# Adapter-Stamps-005.net
KiCad netlist of a schematic drawn in EAGLE
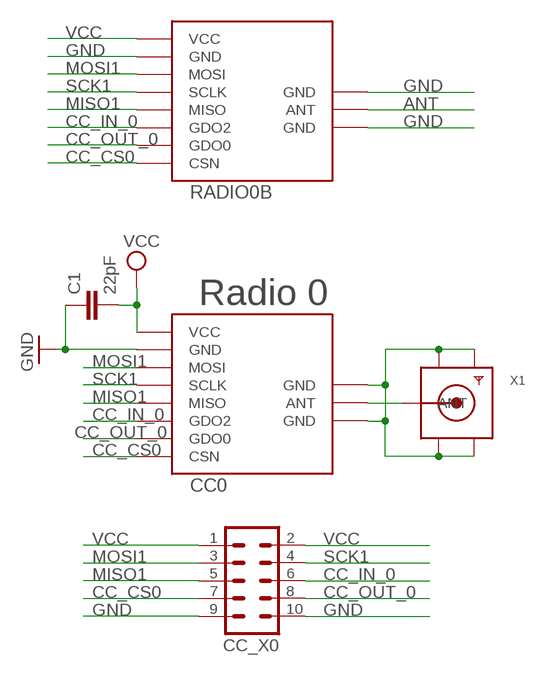
[diagram p0: schematic, sheet 1]

(export (version "E")
  (design (tool "Eeschema 10.0.6"))
  (components
    (comp (ref "C1")
      (value "22pF")
      (footprint "eagle-import:C0805")
      (libsource (lib "eagle-import") (part "C-EUC0805"))
    )
    (comp (ref "CC0")
      (value "CC1101_MODULE1SMD")
      (footprint "eagle-import:CC1101_MODULE1_SMD")
      (libsource (lib "eagle-import") (part "wireless_CC1101_MODULE1SMD"))
    )
    (comp (ref "CC_X0")
      (value "MA05-2")
      (footprint "eagle-import:MA05-2")
      (libsource (lib "eagle-import") (part "MA05-2"))
    )
    (comp (ref "RADIO0B")
      (value "CC1101_MODULE1SMALL")
      (footprint "eagle-import:CC1101_MODULE1_SMD")
      (libsource (lib "eagle-import") (part "CC1101_MODULE1SMALL"))
    )
    (comp (ref "X1")
      (value "SMACONNECTOR_EDGE_UFL")
      (footprint "eagle-import:SMA_EDGELAUNCH_UFL")
      (libsource (lib "eagle-import") (part "SMACONNECTOR_EDGE_UFL"))
    )
  )
  (nets
    (net (code "1") (name "/ANT") (class "Default")
      (node (ref "RADIO0B") (pin "ANT") (pinfunction "ANT_ANT") (pintype "output"))
    )
    (net (code "2") (name "/CC_CS0") (class "Default")
      (node (ref "CC0") (pin "CSN") (pinfunction "CSN_CSN") (pintype "bidirectional"))
      (node (ref "CC_X0") (pin "7") (pinfunction "7_7") (pintype "passive"))
      (node (ref "RADIO0B") (pin "CSN") (pinfunction "CSN_CSN") (pintype "bidirectional"))
    )
    (net (code "3") (name "/CC_IN_0") (class "Default")
      (node (ref "CC0") (pin "GDO2") (pinfunction "GDO2_GDO2") (pintype "bidirectional"))
      (node (ref "CC_X0") (pin "6") (pinfunction "6_6") (pintype "passive"))
      (node (ref "RADIO0B") (pin "GDO2") (pinfunction "GDO2_GDO2") (pintype "bidirectional"))
    )
    (net (code "4") (name "/CC_OUT_0") (class "Default")
      (node (ref "CC0") (pin "GDO0") (pinfunction "GDO0_GDO0") (pintype "bidirectional"))
      (node (ref "CC_X0") (pin "8") (pinfunction "8_8") (pintype "passive"))
      (node (ref "RADIO0B") (pin "GDO0") (pinfunction "GDO0_GDO0") (pintype "bidirectional"))
    )
    (net (code "5") (name "/MISO1") (class "Default")
      (node (ref "CC0") (pin "MISO") (pinfunction "MISO_MISO") (pintype "bidirectional"))
      (node (ref "CC_X0") (pin "5") (pinfunction "5_5") (pintype "passive"))
      (node (ref "RADIO0B") (pin "MISO") (pinfunction "MISO_MISO") (pintype "bidirectional"))
    )
    (net (code "6") (name "/MOSI1") (class "Default")
      (node (ref "CC0") (pin "MOSI") (pinfunction "MOSI_MOSI") (pintype "bidirectional"))
      (node (ref "CC_X0") (pin "3") (pinfunction "3_3") (pintype "passive"))
      (node (ref "RADIO0B") (pin "MOSI") (pinfunction "MOSI_MOSI") (pintype "bidirectional"))
    )
    (net (code "7") (name "/SCK1") (class "Default")
      (node (ref "CC0") (pin "SCLK") (pinfunction "SCLK_SCLK") (pintype "bidirectional"))
      (node (ref "CC_X0") (pin "4") (pinfunction "4_4") (pintype "passive"))
      (node (ref "RADIO0B") (pin "SCLK") (pinfunction "SCLK_SCLK") (pintype "bidirectional"))
    )
    (net (code "8") (name "GND") (class "Default")
      (node (ref "C1") (pin "1") (pinfunction "1_1") (pintype "passive"))
      (node (ref "CC0") (pin "GND@0") (pinfunction "GND_GND@0") (pintype "power_in"))
      (node (ref "CC_X0") (pin "10") (pinfunction "10_10") (pintype "passive"))
      (node (ref "CC_X0") (pin "9") (pinfunction "9_9") (pintype "passive"))
      (node (ref "RADIO0B") (pin "GND@0") (pinfunction "GND_GND@0") (pintype "power_in"))
      (node (ref "RADIO0B") (pin "GND@1") (pinfunction "GND_GND@1") (pintype "power_in"))
      (node (ref "RADIO0B") (pin "GND@2") (pinfunction "GND_GND@2") (pintype "power_in"))
    )
    (net (code "9") (name "Net-(X1-ANT)") (class "Default")
      (node (ref "CC0") (pin "ANT") (pinfunction "ANT_ANT") (pintype "output"))
      (node (ref "X1") (pin "P") (pinfunction "ANT_P") (pintype "bidirectional"))
    )
    (net (code "10") (name "Net-(X1-GND1)") (class "Default")
      (node (ref "CC0") (pin "GND@1") (pinfunction "GND_GND@1") (pintype "power_in"))
      (node (ref "CC0") (pin "GND@2") (pinfunction "GND_GND@2") (pintype "power_in"))
      (node (ref "X1") (pin "GND@1") (pinfunction "GND1_GND@1") (pintype "power_in"))
      (node (ref "X1") (pin "GND@2") (pinfunction "GND2_GND@2") (pintype "power_in"))
      (node (ref "X1") (pin "GND@3") (pinfunction "GND3_GND@3") (pintype "power_in"))
      (node (ref "X1") (pin "GND@4") (pinfunction "GND4_GND@4") (pintype "power_in"))
    )
    (net (code "11") (name "VCC") (class "Default")
      (node (ref "C1") (pin "2") (pinfunction "2_2") (pintype "passive"))
      (node (ref "CC0") (pin "VCC") (pinfunction "VCC_VCC") (pintype "power_in"))
      (node (ref "CC_X0") (pin "1") (pinfunction "1_1") (pintype "passive"))
      (node (ref "CC_X0") (pin "2") (pinfunction "2_2") (pintype "passive"))
      (node (ref "RADIO0B") (pin "VCC") (pinfunction "VCC_VCC") (pintype "power_in"))
    )
  )
)
